# 6coils-1-discrete.net
KiCad netlist of a schematic drawn in EasyEDA
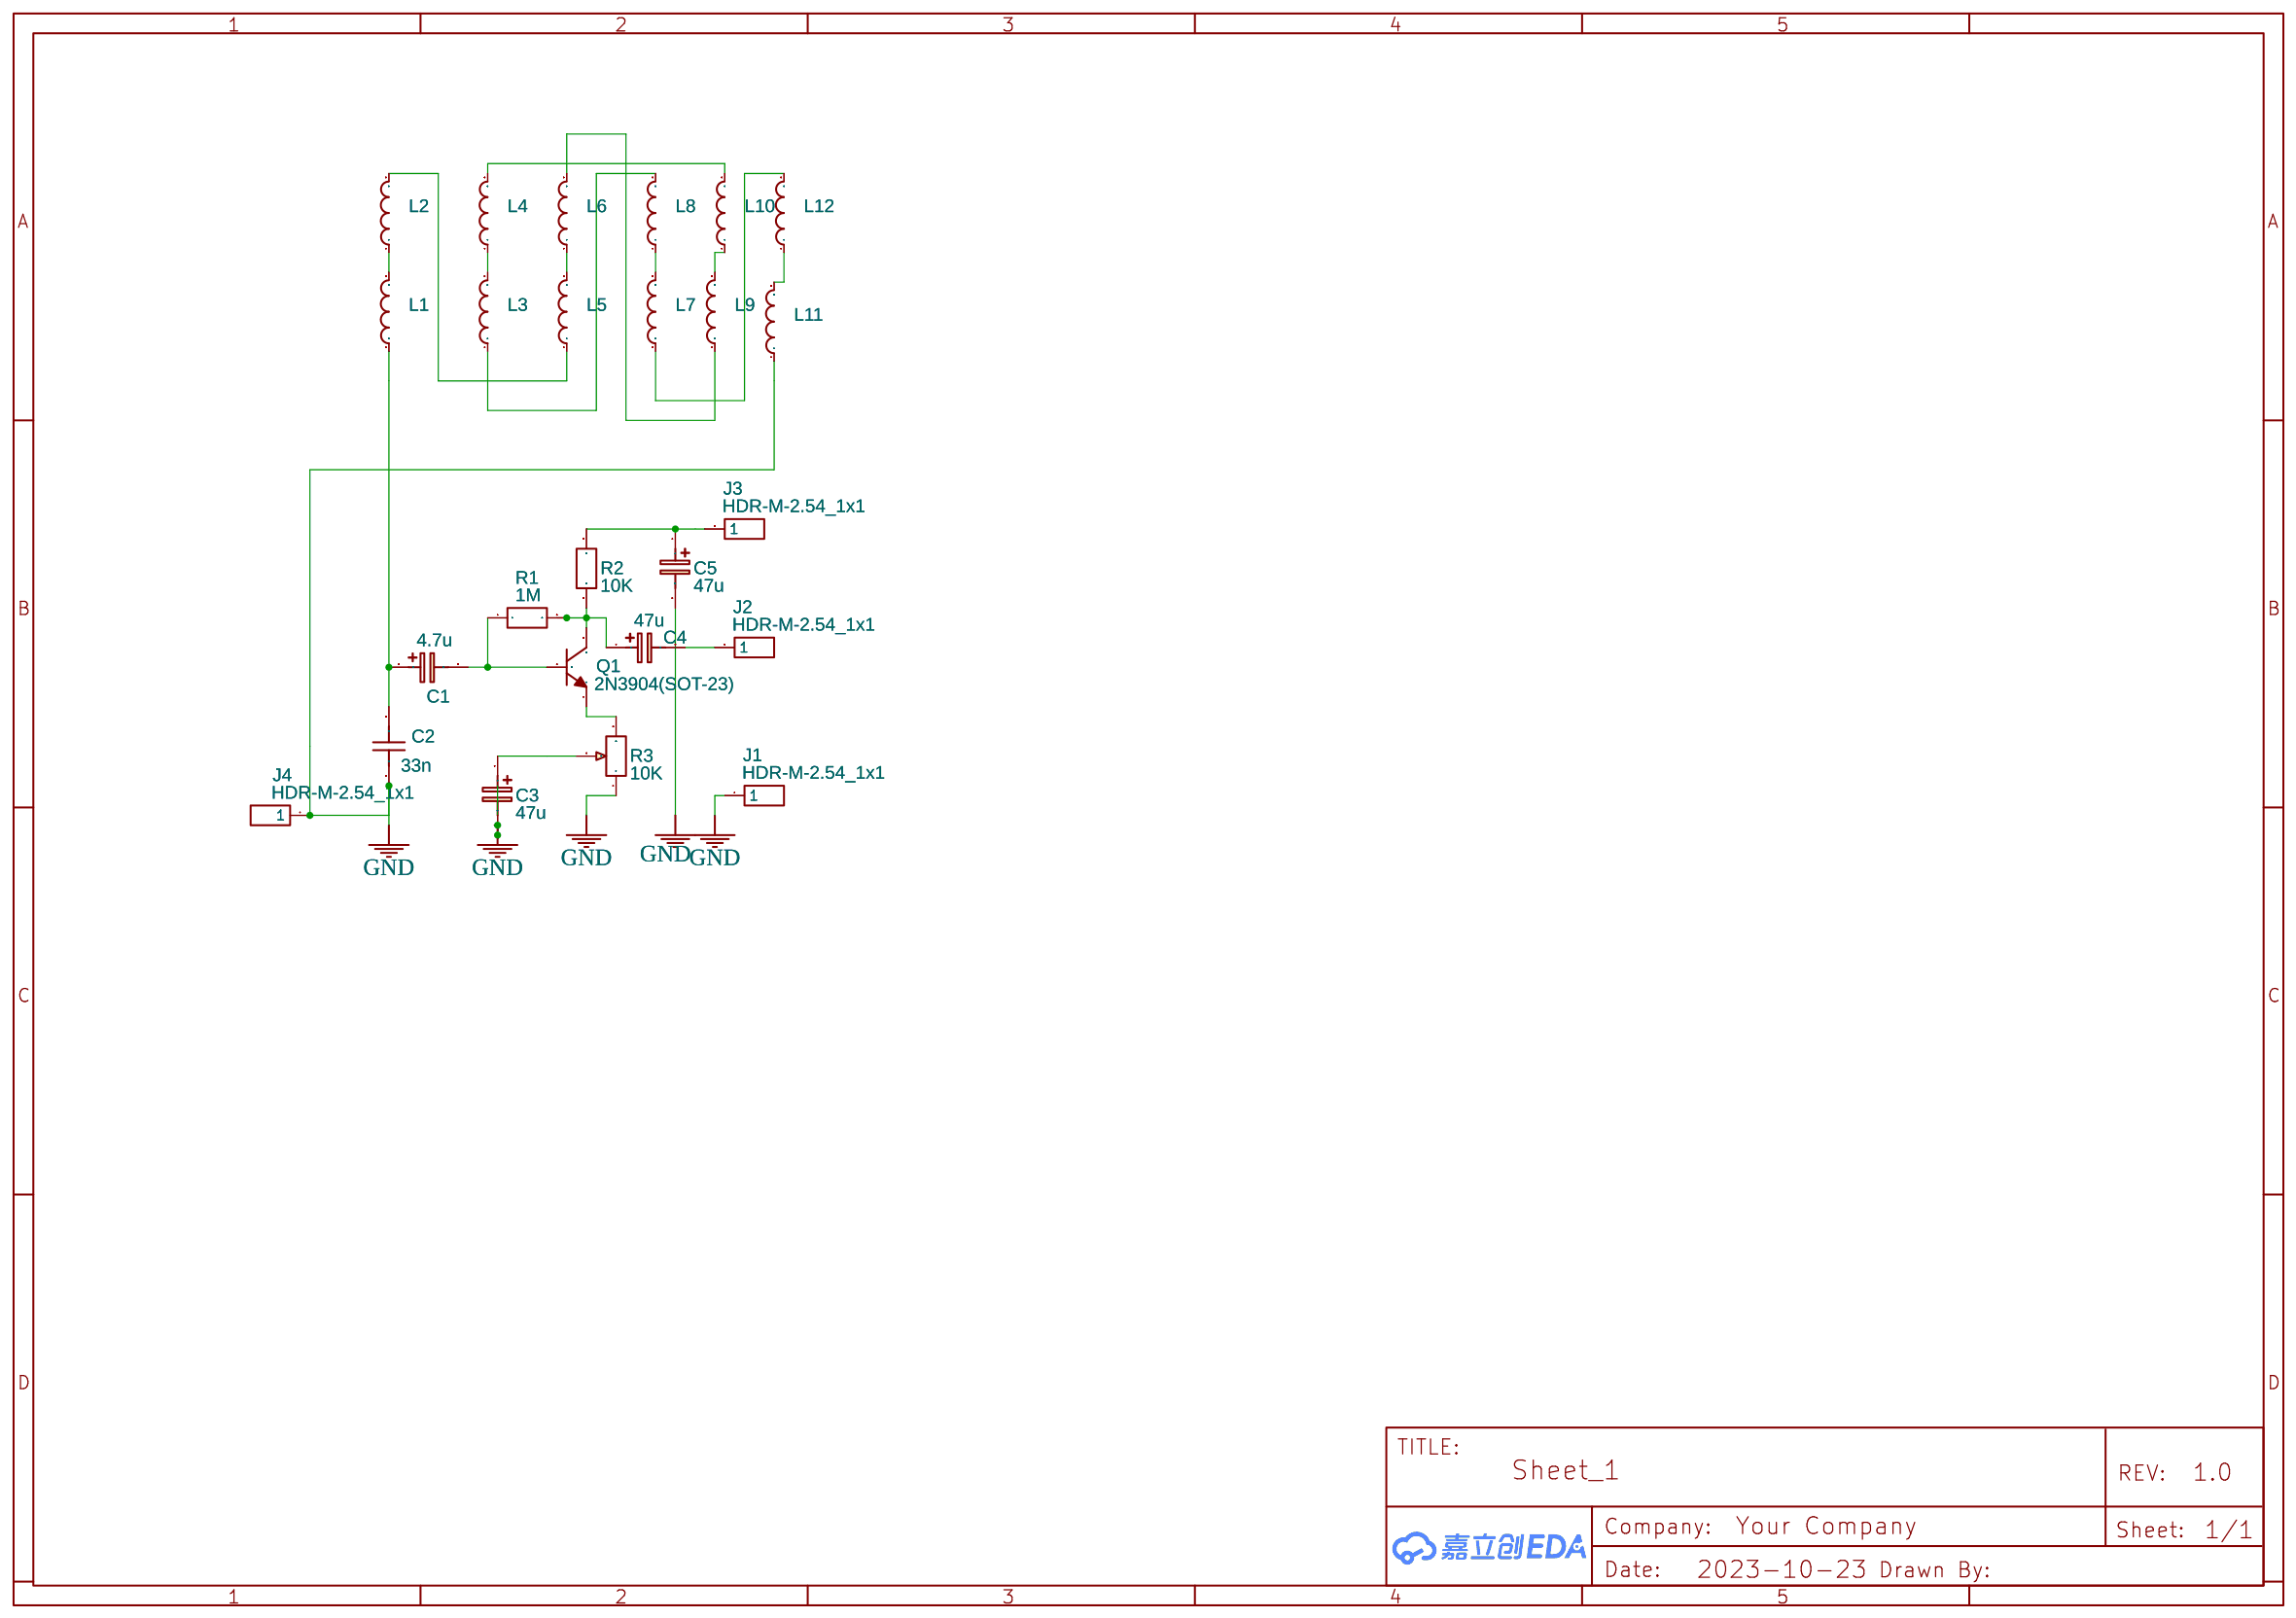
[diagram p0: schematic sheet]

(export (version "E")
  (design (tool "Eeschema 10.0.6"))
  (components
    (comp (ref "C1") (value "4.7u") (libsource (lib "") (part "C_Tan_SMD_A_EU_2")))
    (comp (ref "C2") (value "33n") (libsource (lib "") (part "C_0603_US")))
    (comp (ref "C3") (value "47u") (libsource (lib "") (part "C_Tan_SMD_A_EU_3")))
    (comp (ref "C4") (value "47u") (libsource (lib "") (part "C_Tan_SMD_A_EU_1")))
    (comp (ref "C5") (value "47u") (libsource (lib "") (part "C_Tan_SMD_A_EU")))
    (comp (ref "J1")
      (value "HDR-M-2.54_1x1")
      (fields (field (name "BOM_Supplier Part") "C81276"))
      (libsource (lib "") (part "HDR-M-2.54_1x1"))
    )
    (comp (ref "J2")
      (value "HDR-M-2.54_1x1")
      (fields (field (name "BOM_Supplier Part") "C81276"))
      (libsource (lib "") (part "HDR-M-2.54_1x1"))
    )
    (comp (ref "J3")
      (value "HDR-M-2.54_1x1")
      (fields (field (name "BOM_Supplier Part") "C81276"))
      (libsource (lib "") (part "HDR-M-2.54_1x1"))
    )
    (comp (ref "J4")
      (value "HDR-M-2.54_1x1")
      (fields (field (name "BOM_Supplier Part") "C81276"))
      (libsource (lib "") (part "HDR-M-2.54_1x1_1"))
    )
    (comp (ref "L1")
      (value "INDUCTOR_SMD:L_COILCRAFT_XXL4040")
      (fields (field (name "Manufacturer Part") "Inductor_SMD:L_Coilcraft_XxL4040"))
      (libsource (lib "") (part "INDUCTOR_SMD{colon}L_COILCRAFT_XXL4040_1"))
    )
    (comp (ref "L2")
      (value "INDUCTOR_SMD:L_COILCRAFT_XXL4040")
      (fields (field (name "Manufacturer Part") "Inductor_SMD:L_Coilcraft_XxL4040"))
      (libsource (lib "") (part "INDUCTOR_SMD{colon}L_COILCRAFT_XXL4040_1"))
    )
    (comp (ref "L3")
      (value "INDUCTOR_SMD:L_COILCRAFT_XXL4040")
      (fields (field (name "Manufacturer Part") "Inductor_SMD:L_Coilcraft_XxL4040"))
      (libsource (lib "") (part "INDUCTOR_SMD{colon}L_COILCRAFT_XXL4040_1"))
    )
    (comp (ref "L4")
      (value "INDUCTOR_SMD:L_COILCRAFT_XXL4040")
      (fields (field (name "Manufacturer Part") "Inductor_SMD:L_Coilcraft_XxL4040"))
      (libsource (lib "") (part "INDUCTOR_SMD{colon}L_COILCRAFT_XXL4040_1"))
    )
    (comp (ref "L5")
      (value "INDUCTOR_SMD:L_COILCRAFT_XXL4040")
      (fields (field (name "Manufacturer Part") "Inductor_SMD:L_Coilcraft_XxL4040"))
      (libsource (lib "") (part "INDUCTOR_SMD{colon}L_COILCRAFT_XXL4040"))
    )
    (comp (ref "L6")
      (value "INDUCTOR_SMD:L_COILCRAFT_XXL4040")
      (fields (field (name "Manufacturer Part") "Inductor_SMD:L_Coilcraft_XxL4040"))
      (libsource (lib "") (part "INDUCTOR_SMD{colon}L_COILCRAFT_XXL4040"))
    )
    (comp (ref "L7")
      (value "INDUCTOR_SMD:L_COILCRAFT_XXL4040")
      (fields (field (name "Manufacturer Part") "Inductor_SMD:L_Coilcraft_XxL4040"))
      (libsource (lib "") (part "INDUCTOR_SMD{colon}L_COILCRAFT_XXL4040"))
    )
    (comp (ref "L8")
      (value "INDUCTOR_SMD:L_COILCRAFT_XXL4040")
      (fields (field (name "Manufacturer Part") "Inductor_SMD:L_Coilcraft_XxL4040"))
      (libsource (lib "") (part "INDUCTOR_SMD{colon}L_COILCRAFT_XXL4040"))
    )
    (comp (ref "L9")
      (value "INDUCTOR_SMD:L_COILCRAFT_XXL4040")
      (fields (field (name "Manufacturer Part") "Inductor_SMD:L_Coilcraft_XxL4040"))
      (libsource (lib "") (part "INDUCTOR_SMD{colon}L_COILCRAFT_XXL4040"))
    )
    (comp (ref "L10")
      (value "INDUCTOR_SMD:L_COILCRAFT_XXL4040")
      (fields (field (name "Manufacturer Part") "Inductor_SMD:L_Coilcraft_XxL4040"))
      (libsource (lib "") (part "INDUCTOR_SMD{colon}L_COILCRAFT_XXL4040"))
    )
    (comp (ref "L11")
      (value "INDUCTOR_SMD:L_COILCRAFT_XXL4040")
      (fields (field (name "Manufacturer Part") "Inductor_SMD:L_Coilcraft_XxL4040"))
      (libsource (lib "") (part "INDUCTOR_SMD{colon}L_COILCRAFT_XXL4040"))
    )
    (comp (ref "L12")
      (value "INDUCTOR_SMD:L_COILCRAFT_XXL4040")
      (fields (field (name "Manufacturer Part") "Inductor_SMD:L_Coilcraft_XxL4040"))
      (libsource (lib "") (part "INDUCTOR_SMD{colon}L_COILCRAFT_XXL4040"))
    )
    (comp (ref "Q1")
      (value "2N3904(SOT-23)")
      (fields
        (field (name "BOM_Manufacturer Part") "2n3904S-RTK/PS")
        (field (name "BOM_Supplier Part") "C18536")
      )
      (libsource (lib "") (part "2N3904(SOT-23)"))
    )
    (comp (ref "R1") (value "1M") (libsource (lib "") (part "R_0603_EU")))
    (comp (ref "R2") (value "10K") (libsource (lib "") (part "R_0603_EU_1")))
    (comp (ref "R3")
      (value "10K")
      (fields (field (name "Manufacturer Part") "RM063-103 10K") (field (name "Manufacturer") "JML"))
      (libsource (lib "") (part "RM063-103 10K"))
    )
  )
  (nets
    (net (code "1") (name "GND") (class "Default")
      (node (ref "C2") (pin "1") (pinfunction "1_1") (pintype "unspecified"))
      (node (ref "C3") (pin "2") (pinfunction "2_2") (pintype "unspecified"))
      (node (ref "C5") (pin "2") (pinfunction "2_2") (pintype "unspecified"))
      (node (ref "J1") (pin "1") (pinfunction "1_1") (pintype "input"))
      (node (ref "J4") (pin "1") (pinfunction "1_1") (pintype "input"))
      (node (ref "L11") (pin "1") (pinfunction "1_1") (pintype "unspecified"))
      (node (ref "R3") (pin "1") (pinfunction "1_1") (pintype "input"))
    )
    (net (code "2") (name "Net-(C1-Pad1)") (class "Default")
      (node (ref "C1") (pin "1") (pinfunction "1_1") (pintype "unspecified"))
      (node (ref "C2") (pin "2") (pinfunction "2_2") (pintype "unspecified"))
      (node (ref "L1") (pin "1") (pinfunction "1_1") (pintype "unspecified"))
    )
    (net (code "3") (name "Net-(C3-Pad1)") (class "Default")
      (node (ref "C3") (pin "1") (pinfunction "1_1") (pintype "unspecified"))
      (node (ref "R3") (pin "2") (pinfunction "2_2") (pintype "input"))
    )
    (net (code "4") (name "Net-(C4-Pad2)") (class "Default")
      (node (ref "C4") (pin "2") (pinfunction "2_2") (pintype "unspecified"))
      (node (ref "J2") (pin "1") (pinfunction "1_1") (pintype "input"))
    )
    (net (code "5") (name "Net-(C5-Pad1)") (class "Default")
      (node (ref "C5") (pin "1") (pinfunction "1_1") (pintype "unspecified"))
      (node (ref "J3") (pin "1") (pinfunction "1_1") (pintype "input"))
      (node (ref "R2") (pin "2") (pinfunction "2_2") (pintype "unspecified"))
    )
    (net (code "6") (name "Net-(L1-Pad2)") (class "Default")
      (node (ref "L1") (pin "2") (pinfunction "2_2") (pintype "unspecified"))
      (node (ref "L2") (pin "1") (pinfunction "1_1") (pintype "unspecified"))
    )
    (net (code "7") (name "Net-(L2-Pad2)") (class "Default")
      (node (ref "L2") (pin "2") (pinfunction "2_2") (pintype "unspecified"))
      (node (ref "L5") (pin "1") (pinfunction "1_1") (pintype "unspecified"))
    )
    (net (code "8") (name "Net-(L3-Pad1)") (class "Default")
      (node (ref "L3") (pin "1") (pinfunction "1_1") (pintype "unspecified"))
      (node (ref "L8") (pin "2") (pinfunction "2_2") (pintype "unspecified"))
    )
    (net (code "9") (name "Net-(L3-Pad2)") (class "Default")
      (node (ref "L3") (pin "2") (pinfunction "2_2") (pintype "unspecified"))
      (node (ref "L4") (pin "1") (pinfunction "1_1") (pintype "unspecified"))
    )
    (net (code "10") (name "Net-(L5-Pad2)") (class "Default")
      (node (ref "L5") (pin "2") (pinfunction "2_2") (pintype "unspecified"))
      (node (ref "L6") (pin "1") (pinfunction "1_1") (pintype "unspecified"))
    )
    (net (code "11") (name "Net-(L6-Pad2)") (class "Default")
      (node (ref "L6") (pin "2") (pinfunction "2_2") (pintype "unspecified"))
      (node (ref "L9") (pin "1") (pinfunction "1_1") (pintype "unspecified"))
    )
    (net (code "12") (name "Net-(L7-Pad2)") (class "Default")
      (node (ref "L7") (pin "2") (pinfunction "2_2") (pintype "unspecified"))
      (node (ref "L8") (pin "1") (pinfunction "1_1") (pintype "unspecified"))
    )
    (net (code "13") (name "Net-(L10-Pad1)") (class "Default")
      (node (ref "L10") (pin "1") (pinfunction "1_1") (pintype "unspecified"))
      (node (ref "L9") (pin "2") (pinfunction "2_2") (pintype "unspecified"))
    )
    (net (code "14") (name "Net-(L10-Pad2)") (class "Default")
      (node (ref "L10") (pin "2") (pinfunction "2_2") (pintype "unspecified"))
      (node (ref "L4") (pin "2") (pinfunction "2_2") (pintype "unspecified"))
    )
    (net (code "15") (name "Net-(L11-Pad2)") (class "Default")
      (node (ref "L11") (pin "2") (pinfunction "2_2") (pintype "unspecified"))
      (node (ref "L12") (pin "1") (pinfunction "1_1") (pintype "unspecified"))
    )
    (net (code "16") (name "Net-(L12-Pad2)") (class "Default")
      (node (ref "L12") (pin "2") (pinfunction "2_2") (pintype "unspecified"))
      (node (ref "L7") (pin "1") (pinfunction "1_1") (pintype "unspecified"))
    )
    (net (code "17") (name "Net-(Q1-B)") (class "Default")
      (node (ref "C1") (pin "2") (pinfunction "2_2") (pintype "unspecified"))
      (node (ref "Q1") (pin "2") (pinfunction "B_2") (pintype "input"))
      (node (ref "R1") (pin "1") (pinfunction "1_1") (pintype "unspecified"))
    )
    (net (code "18") (name "Net-(Q1-C)") (class "Default")
      (node (ref "C4") (pin "1") (pinfunction "1_1") (pintype "unspecified"))
      (node (ref "Q1") (pin "3") (pinfunction "C_3") (pintype "input"))
      (node (ref "R1") (pin "2") (pinfunction "2_2") (pintype "unspecified"))
      (node (ref "R2") (pin "1") (pinfunction "1_1") (pintype "unspecified"))
    )
    (net (code "19") (name "Net-(Q1-E)") (class "Default")
      (node (ref "Q1") (pin "1") (pinfunction "E_1") (pintype "input"))
      (node (ref "R3") (pin "3") (pinfunction "3_3") (pintype "input"))
    )
  )
)
